# SCH_MULTIVIBRATOR_Task-1_2021-06-30.net
KiCad netlist of a schematic drawn in EasyEDA
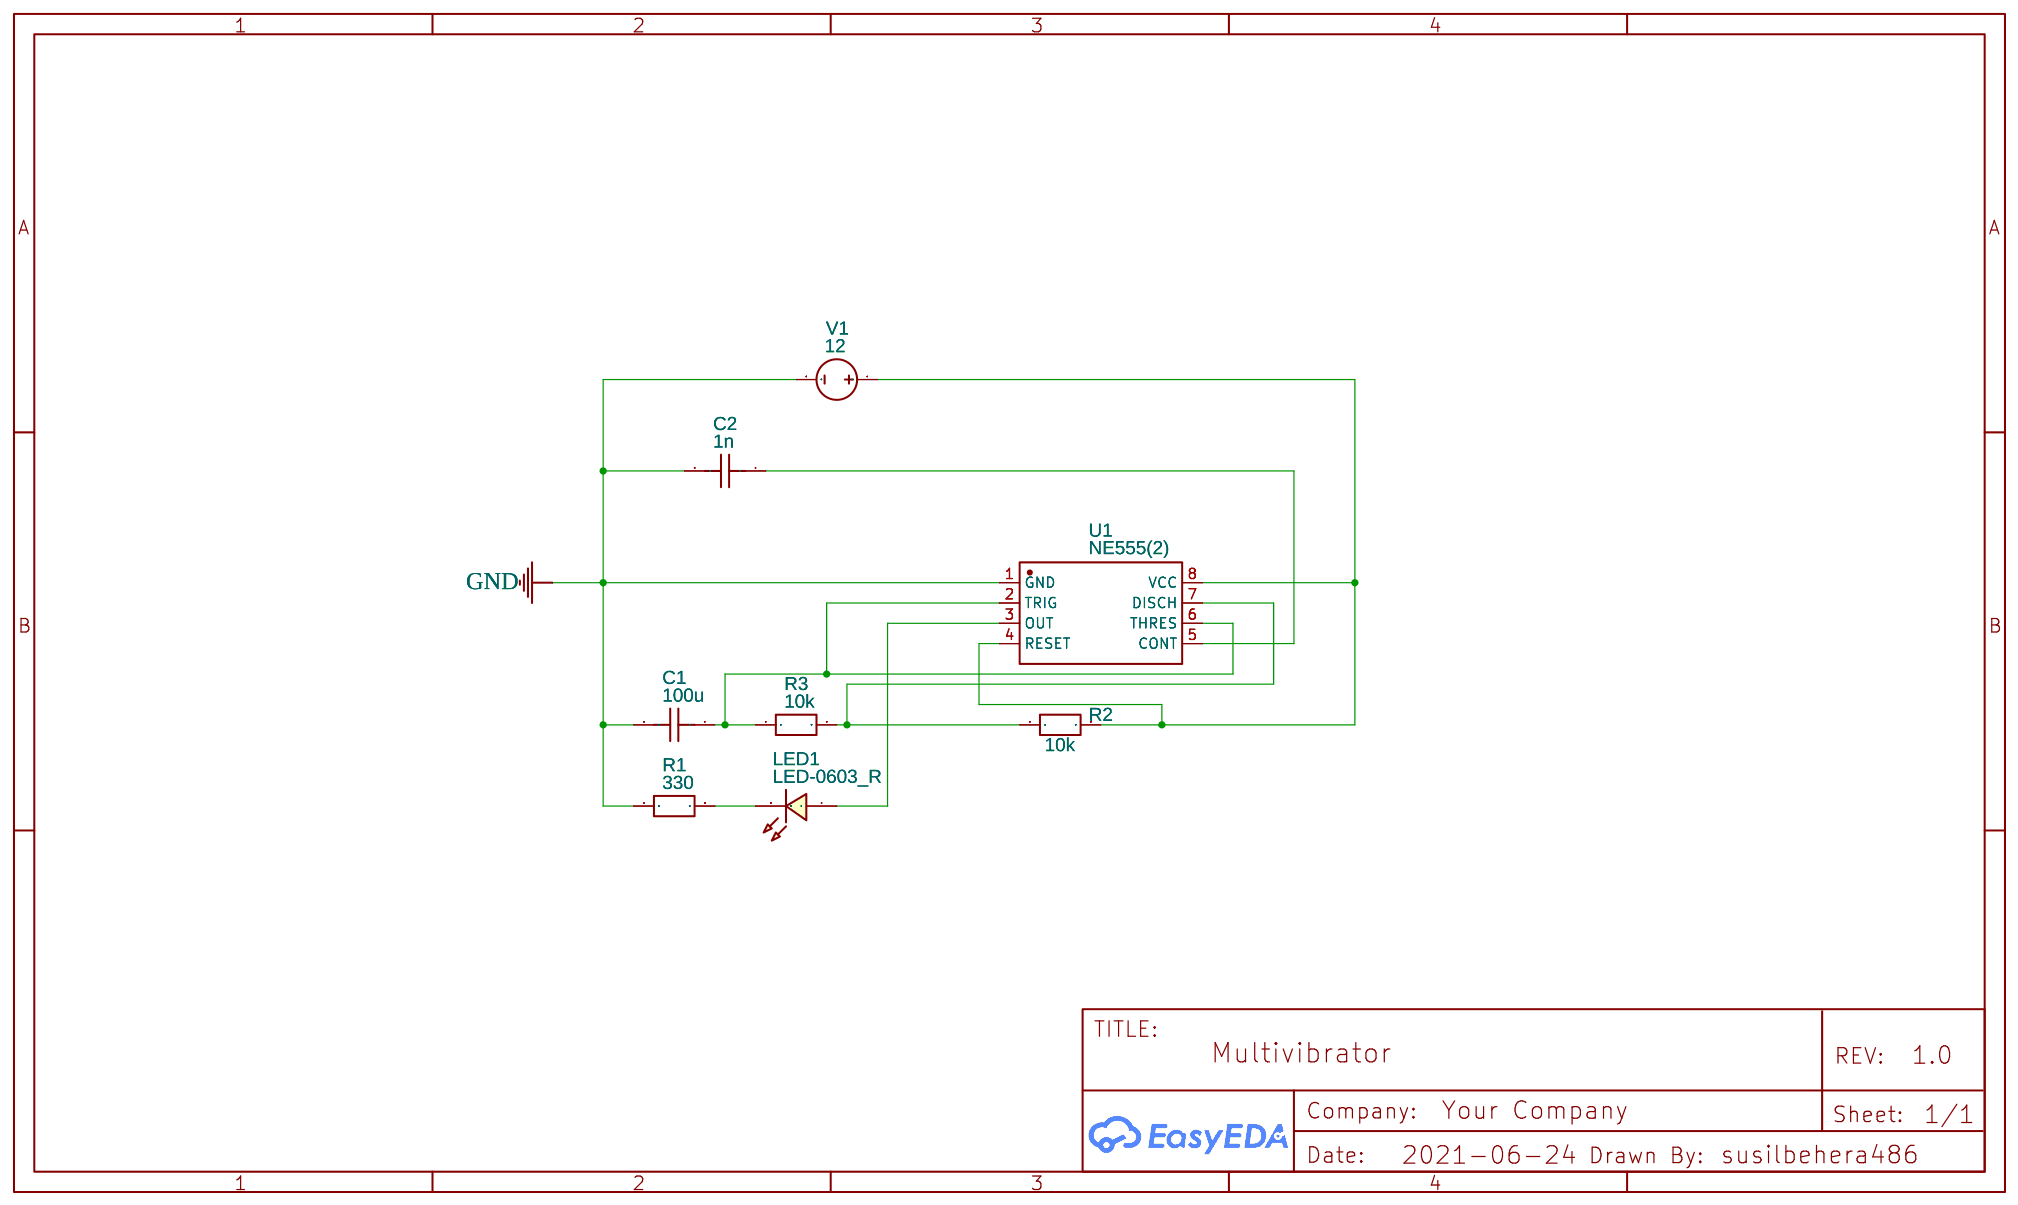
[diagram p0: schematic sheet]

(export (version "E")
  (design (tool "Eeschema 10.0.6"))
  (components
    (comp (ref "C1") (value "100u") (libsource (lib "") (part "C_0603_US")))
    (comp (ref "C2") (value "1n") (libsource (lib "") (part "C_0603_US")))
    (comp (ref "LED1")
      (value "LED-0603_R")
      (fields
        (field (name "BOM_Manufacturer Part") "19-217/R6C-AL1M2VY/3T")
        (field (name "BOM_Supplier Part") "C72044")
      )
      (libsource (lib "") (part "LED-0603_R"))
    )
    (comp (ref "R1") (value "330") (libsource (lib "") (part "R_0603_EU")))
    (comp (ref "R2") (value "10k") (libsource (lib "") (part "R_0603_EU")))
    (comp (ref "R3") (value "10k") (libsource (lib "") (part "R_0603_EU")))
    (comp (ref "U1") (value "NE555(2)") (libsource (lib "") (part "NE555(2)")))
    (comp (ref "V1") (value "12") (libsource (lib "") (part "VDC")))
  )
  (nets
    (net (code "1") (name "GND") (class "Default")
      (node (ref "C1") (pin "2") (pinfunction "2_2") (pintype "unspecified"))
      (node (ref "C2") (pin "2") (pinfunction "2_2") (pintype "unspecified"))
      (node (ref "R1") (pin "1") (pinfunction "1_1") (pintype "unspecified"))
      (node (ref "U1") (pin "1") (pinfunction "GND_1") (pintype "unspecified"))
      (node (ref "V1") (pin "2") (pinfunction "2_2") (pintype "unspecified"))
    )
    (net (code "2") (name "Net-(LED1-Pad2)") (class "Default")
      (node (ref "LED1") (pin "2") (pinfunction "2_2") (pintype "unspecified"))
      (node (ref "R1") (pin "2") (pinfunction "2_2") (pintype "unspecified"))
    )
    (net (code "3") (name "Net-(U1-CONT)") (class "Default")
      (node (ref "C2") (pin "1") (pinfunction "1_1") (pintype "unspecified"))
      (node (ref "U1") (pin "5") (pinfunction "CONT_5") (pintype "unspecified"))
    )
    (net (code "4") (name "Net-(U1-DISCH)") (class "Default")
      (node (ref "R2") (pin "1") (pinfunction "1_1") (pintype "unspecified"))
      (node (ref "R3") (pin "2") (pinfunction "2_2") (pintype "unspecified"))
      (node (ref "U1") (pin "7") (pinfunction "DISCH_7") (pintype "unspecified"))
    )
    (net (code "5") (name "Net-(U1-OUT)") (class "Default")
      (node (ref "LED1") (pin "1") (pinfunction "1_1") (pintype "unspecified"))
      (node (ref "U1") (pin "3") (pinfunction "OUT_3") (pintype "unspecified"))
    )
    (net (code "6") (name "Net-(U1-RESET)") (class "Default")
      (node (ref "R2") (pin "2") (pinfunction "2_2") (pintype "unspecified"))
      (node (ref "U1") (pin "4") (pinfunction "RESET_4") (pintype "unspecified"))
      (node (ref "U1") (pin "8") (pinfunction "VCC_8") (pintype "unspecified"))
      (node (ref "V1") (pin "1") (pinfunction "1_1") (pintype "unspecified"))
    )
    (net (code "7") (name "Net-(U1-THRES)") (class "Default")
      (node (ref "C1") (pin "1") (pinfunction "1_1") (pintype "unspecified"))
      (node (ref "R3") (pin "1") (pinfunction "1_1") (pintype "unspecified"))
      (node (ref "U1") (pin "2") (pinfunction "TRIG_2") (pintype "unspecified"))
      (node (ref "U1") (pin "6") (pinfunction "THRES_6") (pintype "unspecified"))
    )
  )
)
